# LB_BIT_o4_VIBRATIONMOTOR-v02_rev1.net
KiCad netlist of a schematic drawn in EAGLE
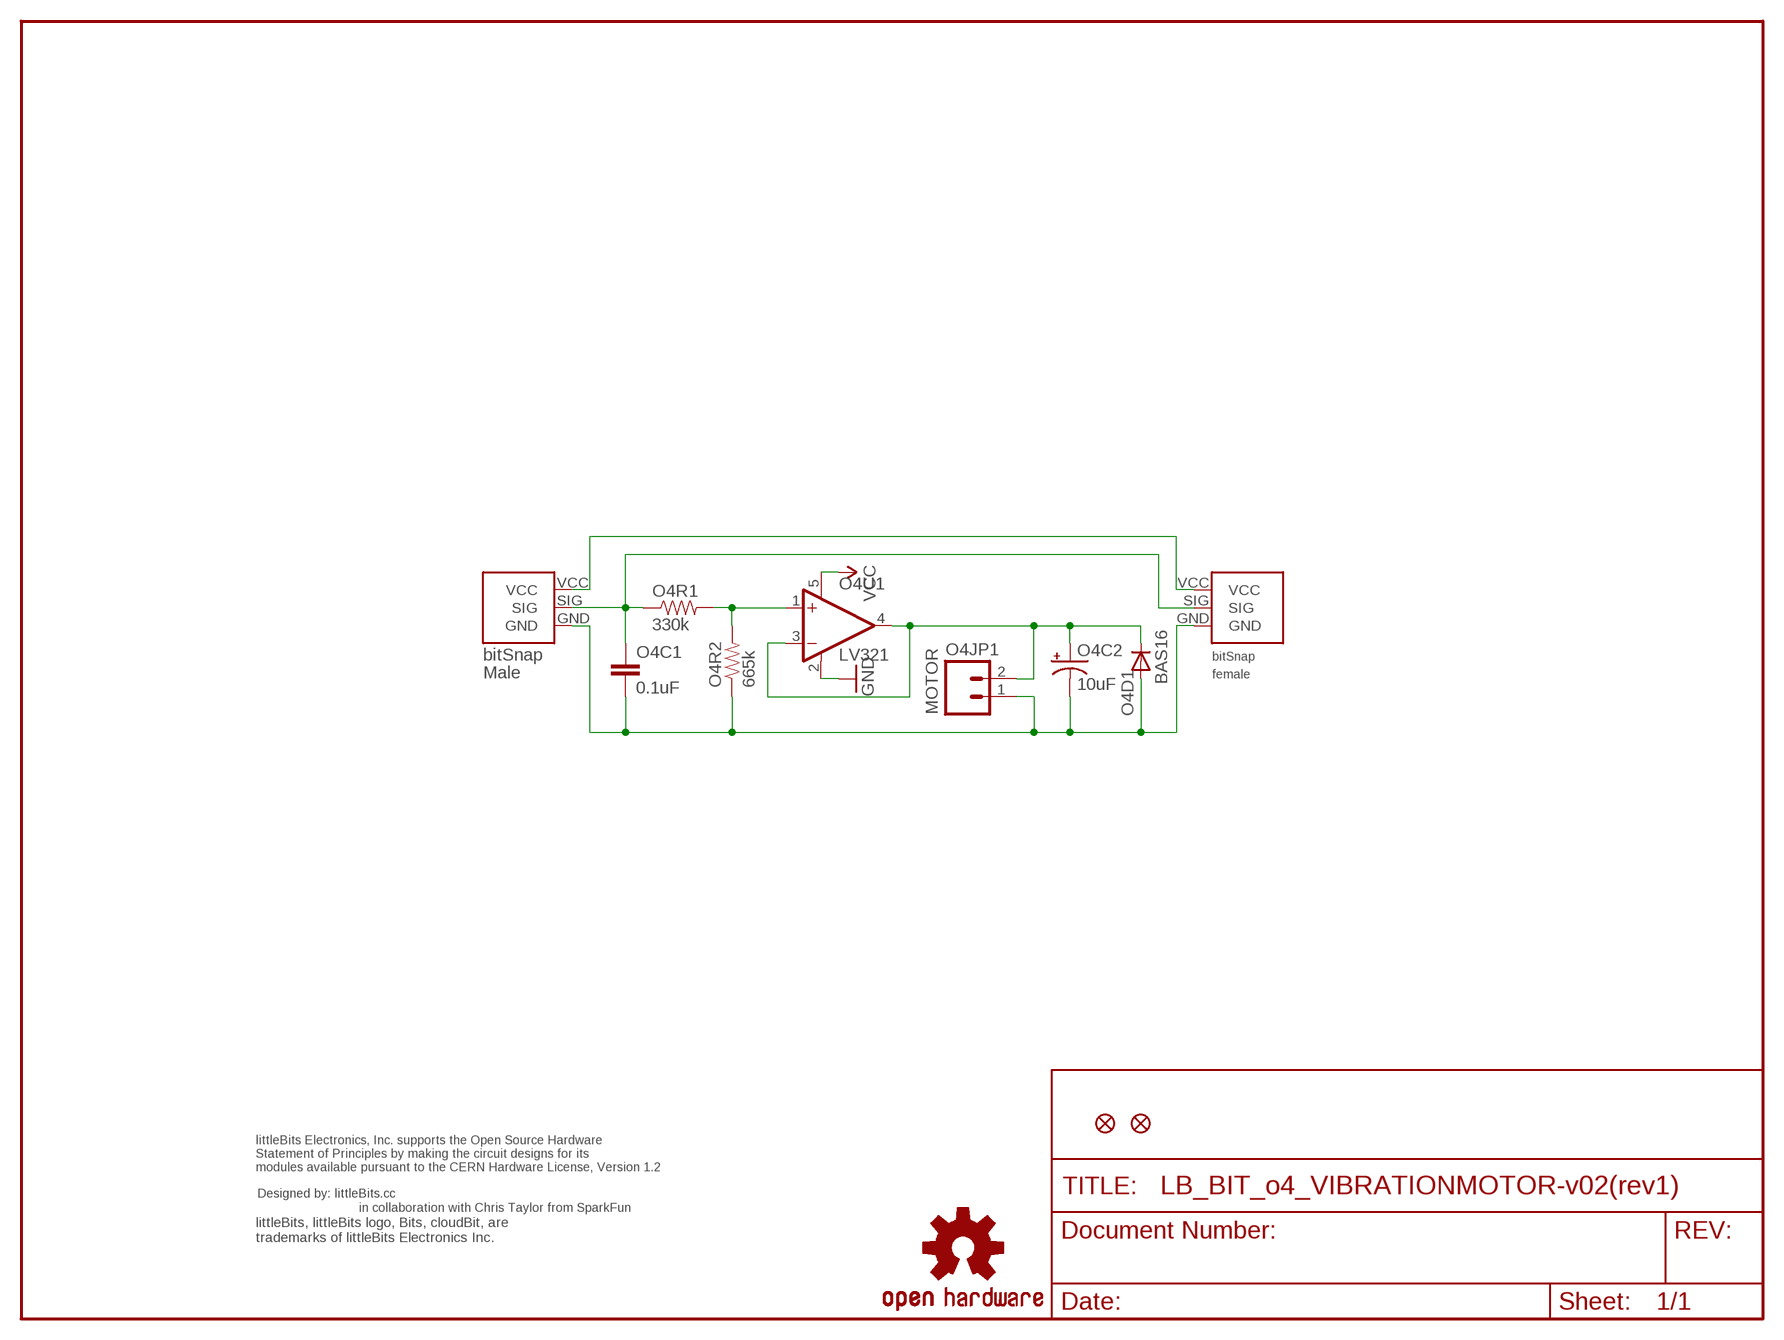
[diagram p0: schematic, sheet 1]

(export (version "E")
  (design (tool "Eeschema 10.0.6"))
  (components
    (comp (ref "JP2")
      (value "FIDUCIAL1X2.5")
      (footprint "eagle-import:FIDUCIAL-1X2.5")
      (libsource (lib "eagle-import") (part "FIDUCIAL1X2.5"))
    )
    (comp (ref "JP3")
      (value "FIDUCIAL1X2.5")
      (footprint "eagle-import:FIDUCIAL-1X2.5")
      (libsource (lib "eagle-import") (part "FIDUCIAL1X2.5"))
    )
    (comp (ref "O4BSF")
      (value "BITSNAP_FEMALE")
      (footprint "eagle-import:BITSNAP_FEMALE")
      (libsource (lib "eagle-import") (part "BITSNAP_FEMALE"))
    )
    (comp (ref "O4BSM")
      (value "BITSNAP_MALE")
      (footprint "eagle-import:BITSNAP_MALE")
      (libsource (lib "eagle-import") (part "BITSNAP_MALE"))
    )
    (comp (ref "O4C1")
      (value "0.1uF")
      (footprint "eagle-import:0603-CAP")
      (libsource (lib "eagle-import") (part "CAP0603-CAP"))
    )
    (comp (ref "O4C2")
      (value "10uF")
      (footprint "eagle-import:EIA3216")
      (libsource (lib "eagle-import") (part "CAP_POL1206"))
    )
    (comp (ref "O4D1")
      (value "BAS16")
      (footprint "eagle-import:SOT23-3")
      (libsource (lib "eagle-import") (part "DIODESOT23"))
    )
    (comp (ref "O4JP1")
      (value "MOTOR")
      (footprint "eagle-import:1X02")
      (libsource (lib "eagle-import") (part "M02PTH"))
    )
    (comp (ref "O4R1")
      (value "330k")
      (footprint "eagle-import:0603-RES")
      (libsource (lib "eagle-import") (part "RESISTOR0603-RES"))
    )
    (comp (ref "O4R2")
      (value "665k")
      (footprint "eagle-import:0603-RES")
      (libsource (lib "eagle-import") (part "RESISTOR0603-RES"))
    )
    (comp (ref "O4U1")
      (value "LV321")
      (footprint "eagle-import:SC70-5")
      (libsource (lib "eagle-import") (part "LV321"))
    )
    (comp (ref "U$1")
      (value "OSHWCREDIT")
      (footprint "eagle-import:OSHWCREDIT")
      (libsource (lib "eagle-import") (part "OSHWCREDIT"))
    )
    (comp (ref "U$5")
      (value "OSHW-LOGOL")
      (footprint "eagle-import:OSHW-LOGO-L")
      (libsource (lib "eagle-import") (part "OSHW-LOGOL"))
    )
  )
  (nets
    (net (code "1") (name "GND") (class "Default")
      (node (ref "O4BSF") (pin "GND") (pinfunction "GND_GND") (pintype "bidirectional"))
      (node (ref "O4BSM") (pin "GND") (pinfunction "GND_GND") (pintype "bidirectional"))
      (node (ref "O4C1") (pin "2") (pinfunction "2_2") (pintype "passive"))
      (node (ref "O4C2") (pin "C") (pinfunction "-_C") (pintype "passive"))
      (node (ref "O4D1") (pin "1") (pinfunction "A_1") (pintype "passive"))
      (node (ref "O4JP1") (pin "1") (pinfunction "1_1") (pintype "passive"))
      (node (ref "O4R2") (pin "1") (pinfunction "1_1") (pintype "passive"))
      (node (ref "O4U1") (pin "2") (pinfunction "V-_2") (pintype "power_in"))
    )
    (net (code "2") (name "Net-(O4BSF-PadSIG)") (class "Default")
      (node (ref "O4BSF") (pin "SIG") (pinfunction "SIG_SIG") (pintype "bidirectional"))
      (node (ref "O4BSM") (pin "SIG") (pinfunction "SIG_SIG") (pintype "bidirectional"))
      (node (ref "O4C1") (pin "1") (pinfunction "1_1") (pintype "passive"))
      (node (ref "O4R1") (pin "1") (pinfunction "1_1") (pintype "passive"))
    )
    (net (code "3") (name "Net-(O4C2-+)") (class "Default")
      (node (ref "O4C2") (pin "A") (pinfunction "+_A") (pintype "passive"))
      (node (ref "O4D1") (pin "3") (pinfunction "C_3") (pintype "passive"))
      (node (ref "O4JP1") (pin "2") (pinfunction "2_2") (pintype "passive"))
      (node (ref "O4U1") (pin "3") (pinfunction "-IN_3") (pintype "input"))
      (node (ref "O4U1") (pin "4") (pinfunction "OUT_4") (pintype "output"))
    )
    (net (code "4") (name "Net-(O4U1-+IN)") (class "Default")
      (node (ref "O4R1") (pin "2") (pinfunction "2_2") (pintype "passive"))
      (node (ref "O4R2") (pin "2") (pinfunction "2_2") (pintype "passive"))
      (node (ref "O4U1") (pin "1") (pinfunction "+IN_1") (pintype "input"))
    )
    (net (code "5") (name "VCC") (class "Default")
      (node (ref "O4BSF") (pin "VCC") (pinfunction "VCC_VCC") (pintype "bidirectional"))
      (node (ref "O4BSM") (pin "VCC") (pinfunction "VCC_VCC") (pintype "bidirectional"))
      (node (ref "O4U1") (pin "5") (pinfunction "V+_5") (pintype "power_in"))
    )
  )
)
